# Serial_Led.net
KiCad netlist of a schematic drawn in Altium Designer
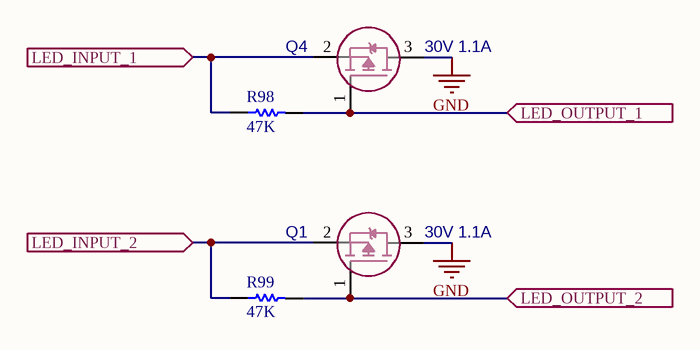
[diagram p0: Serial_Led.SchDoc]

(export (version "E")
  (design (tool "Eeschema 10.0.6"))
  (components
    (comp (ref "Q1")
      (value "30V 1.1A")
      (footprint "SOT23")
      (description "MOSFET DIS.1.1A 30V P-CH SOT23 SMT")
      (fields
        (field (name "MANUFACTURER") "PANJIT")
        (field (name "MANUFACTURER PART NUMBER") "PJA3433_R1_00001")
      )
      (libsource (lib "Semiconductors") (part "PMV65XPVL"))
    )
    (comp (ref "Q4")
      (value "30V 1.1A")
      (footprint "SOT23")
      (description "MOSFET DIS.1.1A 30V P-CH SOT23 SMT")
      (fields
        (field (name "MANUFACTURER") "PANJIT")
        (field (name "MANUFACTURER PART NUMBER") "PJA3433_R1_00001")
      )
      (libsource (lib "Semiconductors") (part "PMV65XPVL"))
    )
    (comp (ref "R98")
      (value "47K")
      (footprint "RES_0603")
      (description "RES 0603 47K Ohms 1% 1/10W-S 100PPM")
      (fields
        (field (name "MANUFACTURER") "ROYALOHM")
        (field (name "MANUFACTURER PART NUMBER") "0603SAF4702T5E")
      )
      (libsource (lib "open-components") (part "RES"))
    )
    (comp (ref "R99")
      (value "47K")
      (footprint "RES_0603")
      (description "RES 0603 47K Ohms 1% 1/10W-S 100PPM")
      (fields
        (field (name "MANUFACTURER") "ROYALOHM")
        (field (name "MANUFACTURER PART NUMBER") "0603SAF4702T5E")
      )
      (libsource (lib "open-components") (part "RES"))
    )
  )
  (nets
    (net (code "1") (name "/LED_INPUT_1") (class "Default")
      (node (ref "Q4") (pin "2") (pinfunction "S_2") (pintype "passive"))
      (node (ref "R98") (pin "1") (pinfunction "1_1") (pintype "passive"))
    )
    (net (code "2") (name "/LED_INPUT_2") (class "Default")
      (node (ref "Q1") (pin "2") (pinfunction "S_2") (pintype "passive"))
      (node (ref "R99") (pin "1") (pinfunction "1_1") (pintype "passive"))
    )
    (net (code "3") (name "/LED_OUTPUT_1") (class "Default")
      (node (ref "Q4") (pin "1") (pinfunction "G_1") (pintype "passive"))
      (node (ref "R98") (pin "2") (pinfunction "2_2") (pintype "passive"))
    )
    (net (code "4") (name "/LED_OUTPUT_2") (class "Default")
      (node (ref "Q1") (pin "1") (pinfunction "G_1") (pintype "passive"))
      (node (ref "R99") (pin "2") (pinfunction "2_2") (pintype "passive"))
    )
    (net (code "5") (name "GND") (class "Default")
      (node (ref "Q1") (pin "3") (pinfunction "D_3") (pintype "passive"))
      (node (ref "Q4") (pin "3") (pinfunction "D_3") (pintype "passive"))
    )
  )
)
